# encoder_module_boardedge.net
KiCad netlist of a schematic drawn in EAGLE
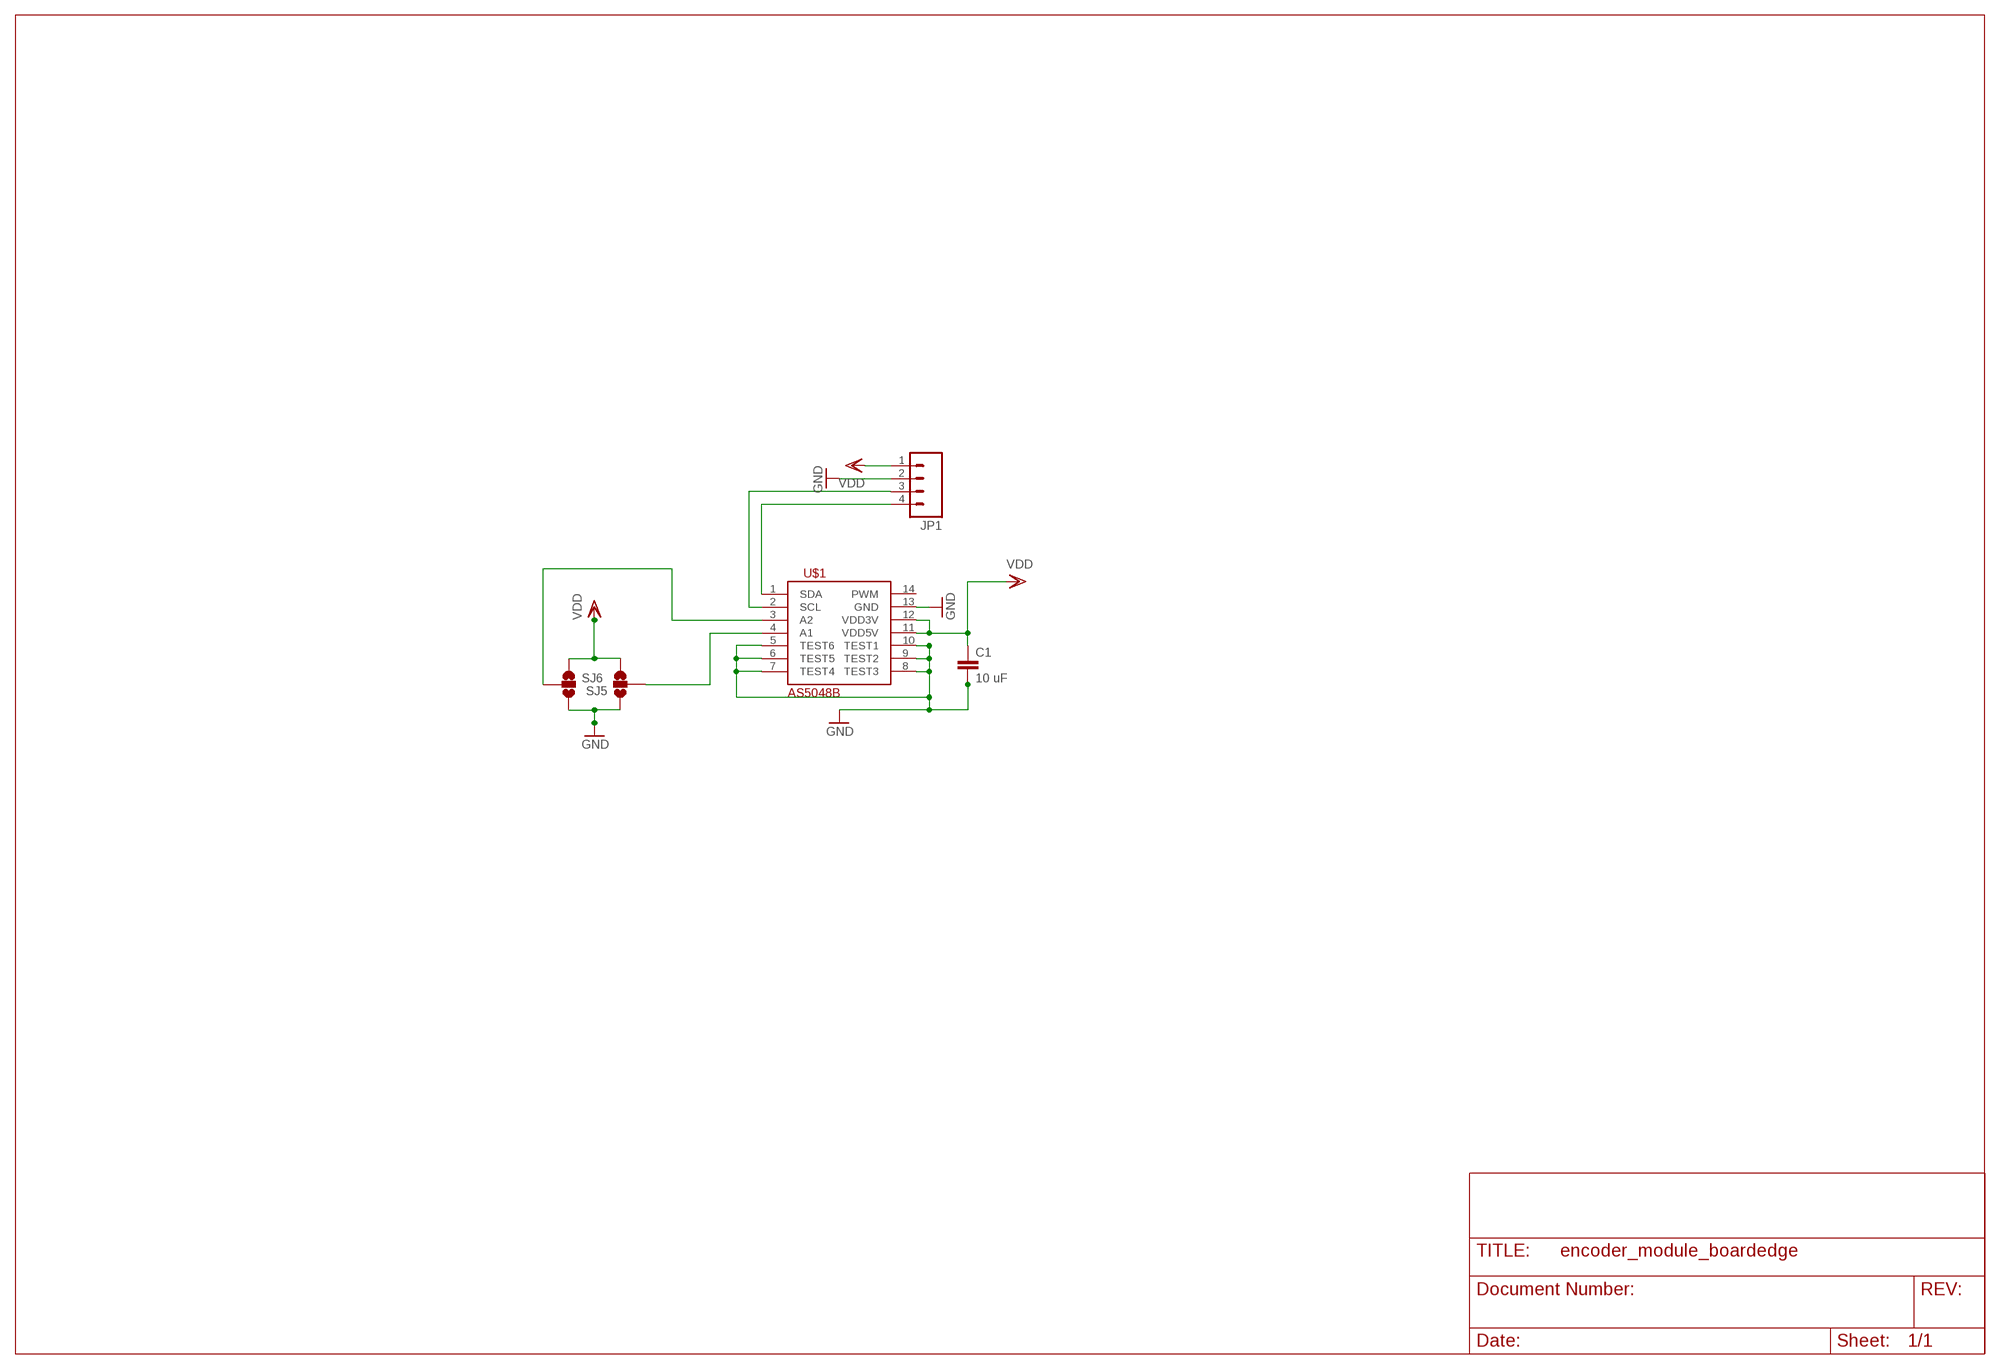
[diagram p0: schematic, sheet 1]

(export (version "E")
  (design (tool "Eeschema 10.0.6"))
  (components
    (comp (ref "C1")
      (value "10 uF")
      (footprint "eagle-import:0603-CAP")
      (libsource (lib "eagle-import") (part "CAP0603-CAP"))
    )
    (comp (ref "JP1")
      (value "M04BOARDEDGE_VERT_VIA")
      (footprint "eagle-import:1X4_3MM_BOARDEDGE_VERT_VIA")
      (libsource (lib "eagle-import") (part "M04BOARDEDGE_VERT_VIA"))
    )
    (comp (ref "SJ5")
      (value "SOLDERJUMPER_2WAYS")
      (footprint "eagle-import:SJ_3")
      (libsource (lib "eagle-import") (part "SOLDERJUMPER_2WAYS"))
    )
    (comp (ref "SJ6")
      (value "SOLDERJUMPER_2WAYS")
      (footprint "eagle-import:SJ_3")
      (libsource (lib "eagle-import") (part "SOLDERJUMPER_2WAYS"))
    )
    (comp (ref "U$1")
      (value "AS5048B")
      (footprint "eagle-import:TSSOP14")
      (libsource (lib "eagle-import") (part "AS5048B"))
    )
  )
  (nets
    (net (code "1") (name "GND") (class "Default")
      (node (ref "C1") (pin "2") (pinfunction "2_2") (pintype "passive"))
      (node (ref "JP1") (pin "2") (pinfunction "2_2") (pintype "passive"))
      (node (ref "SJ5") (pin "1") (pinfunction "1_1") (pintype "passive"))
      (node (ref "SJ6") (pin "3") (pinfunction "3_3") (pintype "passive"))
      (node (ref "U$1") (pin "10") (pinfunction "TEST1_10") (pintype "bidirectional"))
      (node (ref "U$1") (pin "13") (pinfunction "GND_13") (pintype "bidirectional"))
      (node (ref "U$1") (pin "5") (pinfunction "TEST6_5") (pintype "bidirectional"))
      (node (ref "U$1") (pin "6") (pinfunction "TEST5_6") (pintype "bidirectional"))
      (node (ref "U$1") (pin "7") (pinfunction "TEST4_7") (pintype "bidirectional"))
      (node (ref "U$1") (pin "8") (pinfunction "TEST3_8") (pintype "bidirectional"))
      (node (ref "U$1") (pin "9") (pinfunction "TEST2_9") (pintype "bidirectional"))
    )
    (net (code "2") (name "Net-(U$1-A1)") (class "Default")
      (node (ref "SJ5") (pin "2") (pinfunction "2_2") (pintype "passive"))
      (node (ref "U$1") (pin "4") (pinfunction "A1_4") (pintype "bidirectional"))
    )
    (net (code "3") (name "Net-(U$1-A2)") (class "Default")
      (node (ref "SJ6") (pin "2") (pinfunction "2_2") (pintype "passive"))
      (node (ref "U$1") (pin "3") (pinfunction "A2_3") (pintype "bidirectional"))
    )
    (net (code "4") (name "Net-(U$1-SCL)") (class "Default")
      (node (ref "JP1") (pin "3") (pinfunction "3_3") (pintype "passive"))
      (node (ref "U$1") (pin "2") (pinfunction "SCL_2") (pintype "bidirectional"))
    )
    (net (code "5") (name "Net-(U$1-SDA)") (class "Default")
      (node (ref "JP1") (pin "4") (pinfunction "4_4") (pintype "passive"))
      (node (ref "U$1") (pin "1") (pinfunction "SDA_1") (pintype "bidirectional"))
    )
    (net (code "6") (name "VDD") (class "Default")
      (node (ref "C1") (pin "1") (pinfunction "1_1") (pintype "passive"))
      (node (ref "JP1") (pin "1") (pinfunction "1_1") (pintype "passive"))
      (node (ref "SJ5") (pin "3") (pinfunction "3_3") (pintype "passive"))
      (node (ref "SJ6") (pin "1") (pinfunction "1_1") (pintype "passive"))
      (node (ref "U$1") (pin "11") (pinfunction "VDD5V_11") (pintype "bidirectional"))
      (node (ref "U$1") (pin "12") (pinfunction "VDD3V_12") (pintype "bidirectional"))
    )
    (net (code "7") (name "unconnected-(U$1-PWM-Pad14)") (class "Default")
      (node (ref "U$1") (pin "14") (pinfunction "PWM_14") (pintype "bidirectional"))
    )
  )
)
